# PulT__electro.net
KiCad netlist of a schematic drawn in EAGLE
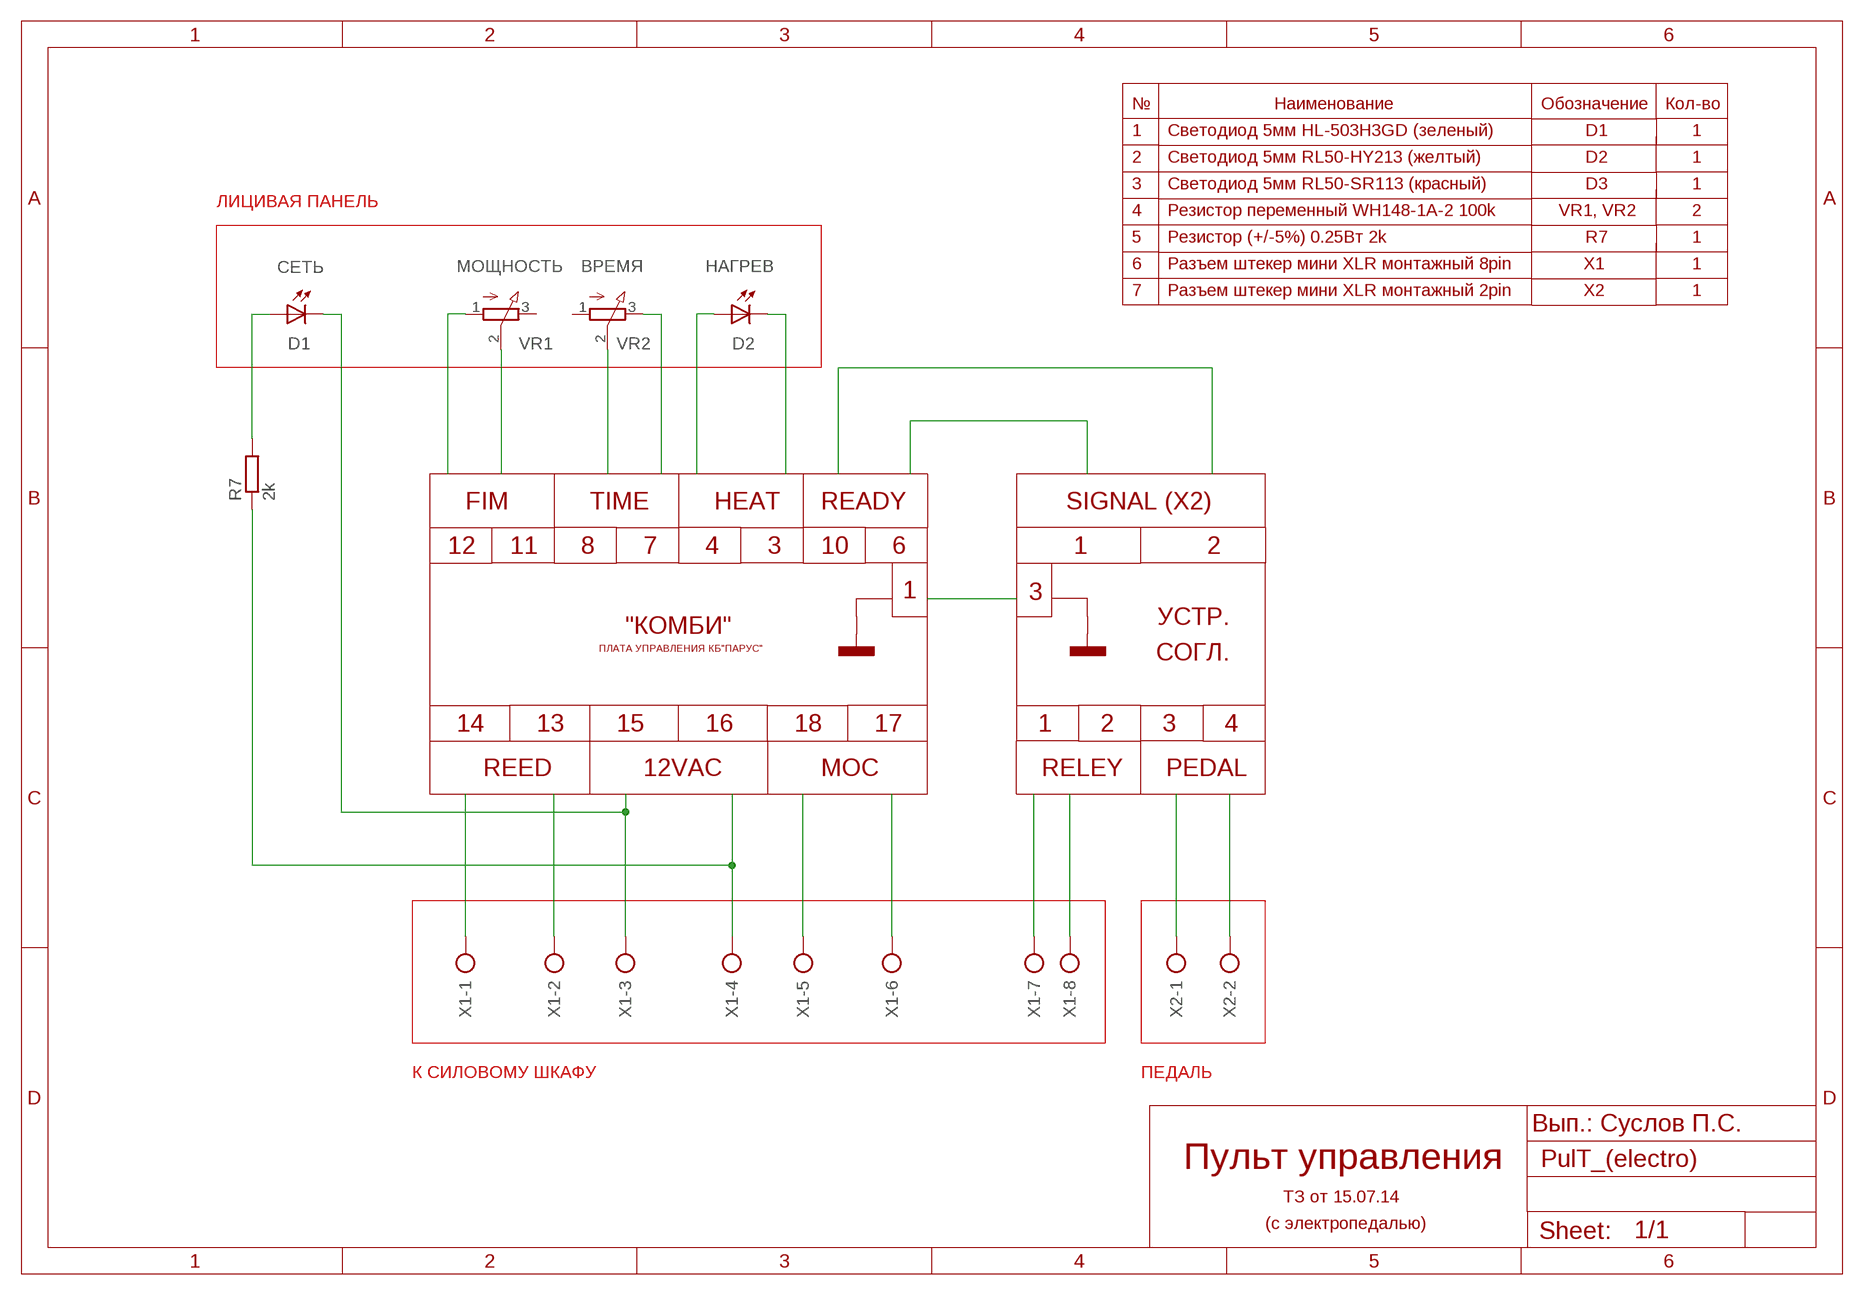
[diagram p0: schematic, sheet 1]

(export (version "E")
  (design (tool "Eeschema 10.0.6"))
  (components
    (comp (ref "G1")
      (value "MASSE_ALLGEMEIN")
      (footprint "eagle-import:MASSE_ALLGEMEIN")
      (libsource (lib "eagle-import") (part "MASSE_ALLGEMEIN"))
    )
    (comp (ref "G2")
      (value "MASSE_ALLGEMEIN")
      (footprint "eagle-import:MASSE_ALLGEMEIN")
      (libsource (lib "eagle-import") (part "MASSE_ALLGEMEIN"))
    )
    (comp (ref "R7")
      (value "2k")
      (footprint "eagle-import:0207_5V")
      (libsource (lib "eagle-import") (part "R-EU_0207/5V"))
    )
    (comp (ref "X1")
      (value "AK500/8")
      (footprint "eagle-import:AK500_8")
      (libsource (lib "eagle-import") (part "AK500/8"))
    )
    (comp (ref "X2")
      (value "AK500/2")
      (footprint "eagle-import:AK500_2")
      (libsource (lib "eagle-import") (part "AK500/2"))
    )
    (comp (ref "ВРЕМЯ")
      (value "3RP/1610N")
      (footprint "eagle-import:3RP_1610N")
      (libsource (lib "eagle-import") (part "3RP/1610N"))
    )
    (comp (ref "ГОТОВ")
      (value "НАГРЕВ")
      (footprint "eagle-import:LED5MM")
      (libsource (lib "eagle-import") (part "LED5MM"))
    )
    (comp (ref "МОЩНОСТЬ")
      (value "3RP/1610N")
      (footprint "eagle-import:3RP_1610N")
      (libsource (lib "eagle-import") (part "3RP/1610N"))
    )
    (comp (ref "СЕТЬ")
      (value "LED5MM")
      (footprint "eagle-import:LED5MM")
      (libsource (lib "eagle-import") (part "LED5MM"))
    )
  )
  (nets
    (net (code "1") (name "Net-(R7-Pad2)") (class "Default")
      (node (ref "R7") (pin "2") (pinfunction "2_2") (pintype "passive"))
      (node (ref "СЕТЬ") (pin "A") (pinfunction "A_A") (pintype "passive"))
    )
    (net (code "2") (name "Net-(X1C-KL)") (class "Default")
      (node (ref "X1") (pin "3") (pinfunction "KL_3") (pintype "passive"))
      (node (ref "СЕТЬ") (pin "K") (pinfunction "C_K") (pintype "passive"))
    )
    (net (code "3") (name "Net-(X1D-KL)") (class "Default")
      (node (ref "R7") (pin "1") (pinfunction "1_1") (pintype "passive"))
      (node (ref "X1") (pin "4") (pinfunction "KL_4") (pintype "passive"))
    )
    (net (code "4") (name "unconnected-(G1-0V-Pad1)") (class "Default")
      (node (ref "G1") (pin "1") (pinfunction "0V_1") (pintype "passive"))
    )
    (net (code "5") (name "unconnected-(G2-0V-Pad1)") (class "Default")
      (node (ref "G2") (pin "1") (pinfunction "0V_1") (pintype "passive"))
    )
    (net (code "6") (name "unconnected-(X1A-KL-Pad1)") (class "Default")
      (node (ref "X1") (pin "1") (pinfunction "KL_1") (pintype "passive"))
    )
    (net (code "7") (name "unconnected-(X1B-KL-Pad2)") (class "Default")
      (node (ref "X1") (pin "2") (pinfunction "KL_2") (pintype "passive"))
    )
    (net (code "8") (name "unconnected-(X1E-KL-Pad5)") (class "Default")
      (node (ref "X1") (pin "5") (pinfunction "KL_5") (pintype "passive"))
    )
    (net (code "9") (name "unconnected-(X1F-KL-Pad6)") (class "Default")
      (node (ref "X1") (pin "6") (pinfunction "KL_6") (pintype "passive"))
    )
    (net (code "10") (name "unconnected-(X1G-KL-Pad7)") (class "Default")
      (node (ref "X1") (pin "7") (pinfunction "KL_7") (pintype "passive"))
    )
    (net (code "11") (name "unconnected-(X1H-KL-Pad8)") (class "Default")
      (node (ref "X1") (pin "8") (pinfunction "KL_8") (pintype "passive"))
    )
    (net (code "12") (name "unconnected-(X2A-KL-Pad1)") (class "Default")
      (node (ref "X2") (pin "1") (pinfunction "KL_1") (pintype "passive"))
    )
    (net (code "13") (name "unconnected-(X2B-KL-Pad2)") (class "Default")
      (node (ref "X2") (pin "2") (pinfunction "KL_2") (pintype "passive"))
    )
    (net (code "14") (name "unconnected-(ВРЕМЯ-A-Pad1)") (class "Default")
      (node (ref "ВРЕМЯ") (pin "1") (pinfunction "A_1") (pintype "passive"))
    )
    (net (code "15") (name "unconnected-(ВРЕМЯ-E-Pad3)") (class "Default")
      (node (ref "ВРЕМЯ") (pin "3") (pinfunction "E_3") (pintype "passive"))
    )
    (net (code "16") (name "unconnected-(ВРЕМЯ-S-Pad2)") (class "Default")
      (node (ref "ВРЕМЯ") (pin "2") (pinfunction "S_2") (pintype "passive"))
    )
    (net (code "17") (name "unconnected-(ГОТОВ-C-PadK)") (class "Default")
      (node (ref "ГОТОВ") (pin "K") (pinfunction "C_K") (pintype "passive"))
    )
    (net (code "18") (name "unconnected-(ГОТОВ-PadA)") (class "Default")
      (node (ref "ГОТОВ") (pin "A") (pinfunction "A_A") (pintype "passive"))
    )
    (net (code "19") (name "unconnected-(МОЩНОСТЬ-A-Pad1)") (class "Default")
      (node (ref "МОЩНОСТЬ") (pin "1") (pinfunction "A_1") (pintype "passive"))
    )
    (net (code "20") (name "unconnected-(МОЩНОСТЬ-E-Pad3)") (class "Default")
      (node (ref "МОЩНОСТЬ") (pin "3") (pinfunction "E_3") (pintype "passive"))
    )
    (net (code "21") (name "unconnected-(МОЩНОСТЬ-S-Pad2)") (class "Default")
      (node (ref "МОЩНОСТЬ") (pin "2") (pinfunction "S_2") (pintype "passive"))
    )
  )
)
